# AIM2_-_FTDI_REVB.net
KiCad netlist of a schematic drawn in Altium Designer
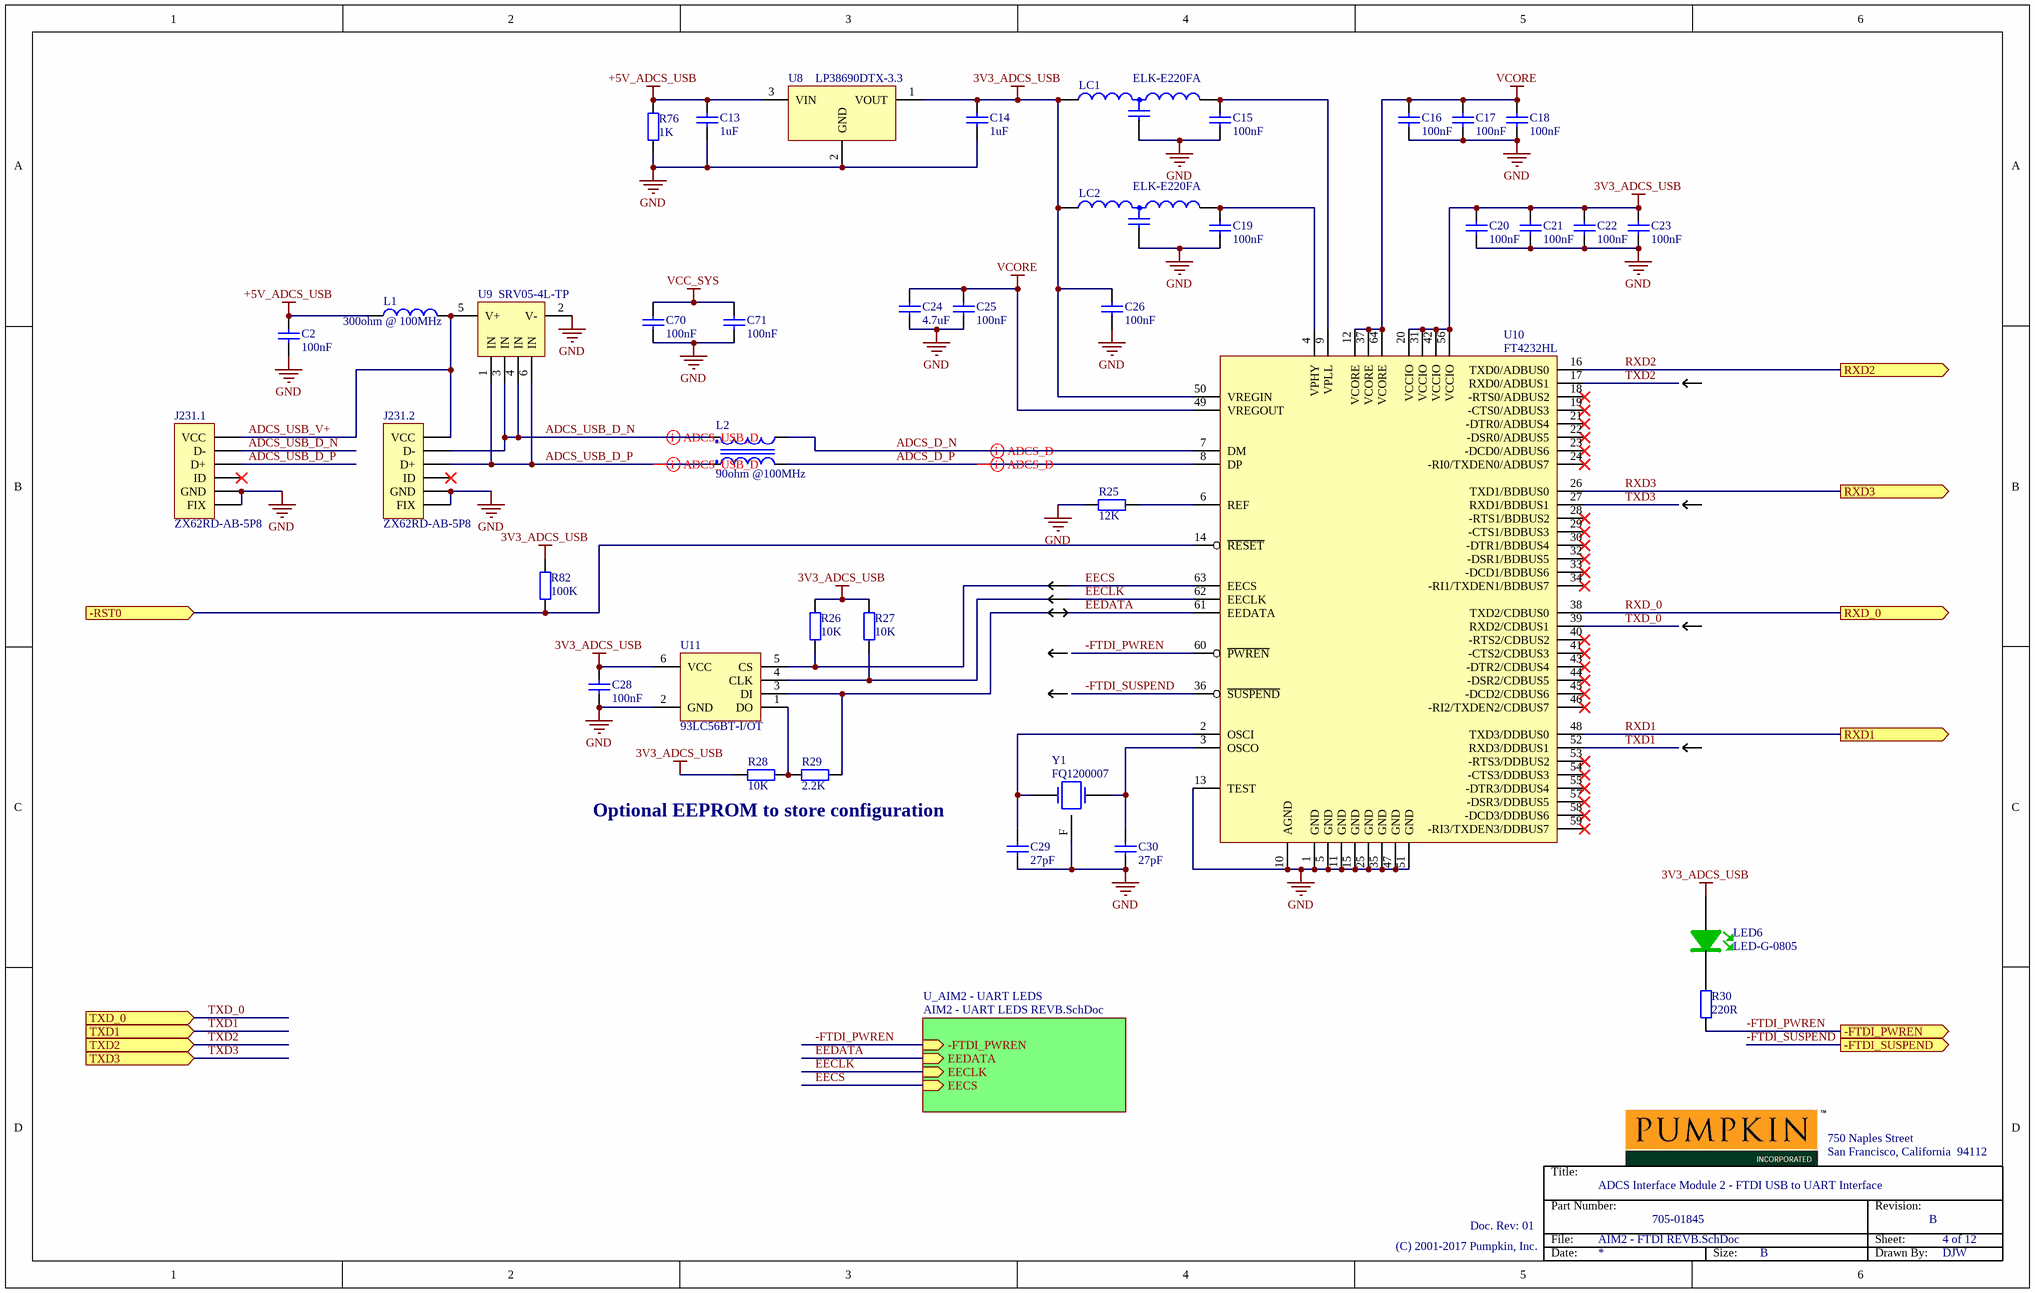
[diagram p0: AIM2 - FTDI REVB.SchDoc]

(export (version "E")
  (design (tool "Eeschema 10.0.6"))
  (components
    (comp (ref "C2")
      (value "100nF")
      (footprint "0603 CAP")
      (description "Capacitor 100nF 0603 X7R 50V 5%")
      (libsource (lib "Supernova passives") (part "Capacitor 100nF 0603"))
    )
    (comp (ref "C13")
      (value "1uF")
      (footprint "0805 CAP")
      (description "Capacitor 1uF 0805 X7R 25V 10%")
      (libsource (lib "Supernova passives") (part "Capacitor 1uF 0805"))
    )
    (comp (ref "C14")
      (value "1uF")
      (footprint "0805 CAP")
      (description "Capacitor 1uF 0805 X7R 25V 10%")
      (libsource (lib "Supernova passives") (part "Capacitor 1uF 0805"))
    )
    (comp (ref "C15")
      (value "100nF")
      (footprint "0603 CAP")
      (description "Capacitor 100nF 0603 X7R 50V 5%")
      (libsource (lib "Supernova passives") (part "Capacitor 100nF 0603"))
    )
    (comp (ref "C16")
      (value "100nF")
      (footprint "0603 CAP")
      (description "Capacitor 100nF 0603 X7R 50V 5%")
      (libsource (lib "Supernova passives") (part "Capacitor 100nF 0603"))
    )
    (comp (ref "C17")
      (value "100nF")
      (footprint "0603 CAP")
      (description "Capacitor 100nF 0603 X7R 50V 5%")
      (libsource (lib "Supernova passives") (part "Capacitor 100nF 0603"))
    )
    (comp (ref "C18")
      (value "100nF")
      (footprint "0603 CAP")
      (description "Capacitor 100nF 0603 X7R 50V 5%")
      (libsource (lib "Supernova passives") (part "Capacitor 100nF 0603"))
    )
    (comp (ref "C19")
      (value "100nF")
      (footprint "0603 CAP")
      (description "Capacitor 100nF 0603 X7R 50V 5%")
      (libsource (lib "Supernova passives") (part "Capacitor 100nF 0603"))
    )
    (comp (ref "C20")
      (value "100nF")
      (footprint "0603 CAP")
      (description "Capacitor 100nF 0603 X7R 50V 5%")
      (libsource (lib "Supernova passives") (part "Capacitor 100nF 0603"))
    )
    (comp (ref "C21")
      (value "100nF")
      (footprint "0603 CAP")
      (description "Capacitor 100nF 0603 X7R 50V 5%")
      (libsource (lib "Supernova passives") (part "Capacitor 100nF 0603"))
    )
    (comp (ref "C22")
      (value "100nF")
      (footprint "0603 CAP")
      (description "Capacitor 100nF 0603 X7R 50V 5%")
      (libsource (lib "Supernova passives") (part "Capacitor 100nF 0603"))
    )
    (comp (ref "C23")
      (value "100nF")
      (footprint "0603 CAP")
      (description "Capacitor 100nF 0603 X7R 50V 5%")
      (libsource (lib "Supernova passives") (part "Capacitor 100nF 0603"))
    )
    (comp (ref "C24")
      (value "4.7uF")
      (footprint "0805 CAP")
      (description "Capacitor 4.7uF 0805 X7R 35V 10%")
      (libsource (lib "Supernova passives") (part "Capacitor 4.7uF 0805"))
    )
    (comp (ref "C25")
      (value "100nF")
      (footprint "0603 CAP")
      (description "Capacitor 100nF 0603 X7R 50V 5%")
      (libsource (lib "Supernova passives") (part "Capacitor 100nF 0603"))
    )
    (comp (ref "C26")
      (value "100nF")
      (footprint "0603 CAP")
      (description "Capacitor 100nF 0603 X7R 50V 5%")
      (libsource (lib "Supernova passives") (part "Capacitor 100nF 0603"))
    )
    (comp (ref "C28")
      (value "100nF")
      (footprint "0603 CAP")
      (description "Capacitor 100nF 0603 X7R 50V 5%")
      (libsource (lib "Supernova passives") (part "Capacitor 100nF 0603"))
    )
    (comp (ref "C29")
      (value "27pF")
      (footprint "0402 CAP")
      (description "Capacitor 27pF 0402 NP0 50V 1%")
      (libsource (lib "Supernova passives") (part "Capacitor 27pF 0402"))
    )
    (comp (ref "C30")
      (value "27pF")
      (footprint "0402 CAP")
      (description "Capacitor 27pF 0402 NP0 50V 1%")
      (libsource (lib "Supernova passives") (part "Capacitor 27pF 0402"))
    )
    (comp (ref "C70")
      (value "100nF")
      (footprint "0603 CAP")
      (description "Capacitor 100nF 0603 X7R 50V 5%")
      (libsource (lib "Supernova passives") (part "Capacitor 100nF 0603"))
    )
    (comp (ref "C71")
      (value "100nF")
      (footprint "0603 CAP")
      (description "Capacitor 100nF 0603 X7R 50V 5%")
      (libsource (lib "Supernova passives") (part "Capacitor 100nF 0603"))
    )
    (comp (ref "J231.1")
      (value "ZX62RD-AB-5P8")
      (footprint "SM$5C$ZX62RD-AB-5P8")
      (description "Header USB Micro AB")
      (libsource (lib "Supernova") (part "ZX62RD-AB-5P8"))
    )
    (comp (ref "J231.2")
      (value "ZX62RD-AB-5P8")
      (footprint "SM$5C$ZX62RD-AB-5P8")
      (description "Header USB Micro AB")
      (libsource (lib "Supernova") (part "ZX62RD-AB-5P8"))
    )
    (comp (ref "L1")
      (value "300ohm @ 100MHz")
      (footprint "0603 IND")
      (description "Ferrite Bead 300ohm @ 100MHz")
      (libsource (lib "Supernova passives") (part "Ferrite Bead 300ohm @ 100MHz"))
    )
    (comp (ref "L2")
      (value "90ohm @100MHz")
      (footprint "DFN250P320X200-4N")
      (description "Choke Common-mode 90ohm @ 100MHz")
      (libsource (lib "Supernova passives") (part "Choke 90ohm @ 100MHz"))
    )
    (comp (ref "LC1")
      (value "ELK-E220FA")
      (footprint "ELK")
      (description "Filter LC 100MHz")
      (libsource (lib "Supernova passives") (part "LC Filter"))
    )
    (comp (ref "LC2")
      (value "ELK-E220FA")
      (footprint "ELK")
      (description "Filter LC 100MHz")
      (libsource (lib "Supernova passives") (part "LC Filter"))
    )
    (comp (ref "LED6")
      (value "LED-G-0805")
      (footprint "0805 LED-GREEN")
      (description "LED Green 0805")
      (libsource (lib "Supernova passives") (part "LED GREEN 0805"))
    )
    (comp (ref "R25")
      (value "12K")
      (footprint "0603 RES")
      (description "Resistor 12K 0603 0.1W 1%")
      (libsource (lib "Supernova passives") (part "Resistor 12K 0603"))
    )
    (comp (ref "R26")
      (value "10K")
      (footprint "0805 RES")
      (description "Resistor 10K 0805 0.125W 1%")
      (libsource (lib "Supernova passives") (part "Resistor 10K 0805"))
    )
    (comp (ref "R27")
      (value "10K")
      (footprint "0805 RES")
      (description "Resistor 10K 0805 0.125W 1%")
      (libsource (lib "Supernova passives") (part "Resistor 10K 0805"))
    )
    (comp (ref "R28")
      (value "10K")
      (footprint "0805 RES")
      (description "Resistor 10K 0805 0.125W 1%")
      (libsource (lib "") (part "Resistor 10K 0805_1"))
    )
    (comp (ref "R29")
      (value "2.2K")
      (footprint "0805 RES")
      (description "Resistor 2.2K 0805 0.125W 1%")
      (libsource (lib "Supernova passives") (part "Resistor 2K2 0805"))
    )
    (comp (ref "R30")
      (value "220R")
      (footprint "0805 RES")
      (description "Resistor 220R 0805 0.125W 1%")
      (libsource (lib "Supernova passives") (part "Resistor 220R 0805"))
    )
    (comp (ref "R76")
      (value "1K")
      (footprint "0805 RES")
      (description "Resistor 1K 0805 0.125W 1%")
      (libsource (lib "Supernova passives") (part "Resistor 1K 0805"))
    )
    (comp (ref "R82")
      (value "100K")
      (footprint "0805 RES")
      (description "Resistor 100K 0805 0.5W 1%")
      (libsource (lib "Supernova passives") (part "Resistor 100K 0805"))
    )
    (comp (ref "U8")
      (value "LP38690DTX-3.3")
      (footprint "DPAK")
      (description "Regulator 3.3V LDO")
      (libsource (lib "Supernova") (part "LP38690DTX-3.3"))
    )
    (comp (ref "U9")
      (value "SRV05-4L-TP")
      (footprint "SOT23-6")
      (description "IC ESD protection 4 input")
      (libsource (lib "Supernova") (part "SRV05-4L-TP"))
    )
    (comp (ref "U10")
      (value "FT4232HL")
      (footprint "TSQFP50P1200X1200X120_HS-65N")
      (description "IC FTDI 4 port controller")
      (libsource (lib "Supernova") (part "FT4232HL"))
    )
    (comp (ref "U11")
      (value "93LC56BT-I/OT")
      (footprint "SOT23-6")
      (description "IC Memory EEPROM 2Kbit")
      (libsource (lib "Supernova") (part "93LC56BT-I/OT"))
    )
    (comp (ref "Y1")
      (value "FQ1200007")
      (footprint "FQ Crystal")
      (description "Crystal 12MHz")
      (libsource (lib "Supernova") (part "FQ1200007"))
    )
  )
  (nets
    (net (code "1") (name "+5V_ADCS_USB") (class "Default")
      (node (ref "C13") (pin "2") (pinfunction "2_2") (pintype "passive"))
      (node (ref "C2") (pin "2") (pinfunction "2_2") (pintype "passive"))
      (node (ref "L1") (pin "1") (pinfunction "1_1") (pintype "passive"))
      (node (ref "R76") (pin "2") (pinfunction "2_2") (pintype "passive"))
      (node (ref "U8") (pin "3") (pinfunction "VIN_3") (pintype "passive"))
    )
    (net (code "2") (name "/-FTDI_PWREN") (class "Default")
      (node (ref "R30") (pin "1") (pinfunction "1_1") (pintype "passive"))
      (node (ref "U10") (pin "60") (pinfunction "~{PWREN}_60") (pintype "passive"))
    )
    (net (code "3") (name "/-FTDI_SUSPEND") (class "Default")
      (node (ref "U10") (pin "36") (pinfunction "~{SUSPEND}_36") (pintype "passive"))
    )
    (net (code "4") (name "/-RST0") (class "Default")
      (node (ref "R82") (pin "1") (pinfunction "1_1") (pintype "passive"))
      (node (ref "U10") (pin "14") (pinfunction "~{RESET}_14") (pintype "passive"))
    )
    (net (code "5") (name "/ADCS_D_N") (class "Default")
      (node (ref "L2") (pin "3") (pinfunction "3_3") (pintype "passive"))
      (node (ref "U10") (pin "7") (pinfunction "DM_7") (pintype "passive"))
    )
    (net (code "6") (name "/ADCS_D_P") (class "Default")
      (node (ref "L2") (pin "2") (pinfunction "2_2") (pintype "passive"))
      (node (ref "U10") (pin "8") (pinfunction "DP_8") (pintype "passive"))
    )
    (net (code "7") (name "/ADCS_USB_D_N") (class "Default")
      (node (ref "J231.1") (pin "2") (pinfunction "D-_2") (pintype "passive"))
      (node (ref "J231.2") (pin "2") (pinfunction "D-_2") (pintype "passive"))
      (node (ref "L2") (pin "4") (pinfunction "4_4") (pintype "passive"))
      (node (ref "U9") (pin "3") (pinfunction "IN_3") (pintype "passive"))
      (node (ref "U9") (pin "4") (pinfunction "IN_4") (pintype "passive"))
    )
    (net (code "8") (name "/ADCS_USB_D_P") (class "Default")
      (node (ref "J231.1") (pin "3") (pinfunction "D+_3") (pintype "passive"))
      (node (ref "J231.2") (pin "3") (pinfunction "D+_3") (pintype "passive"))
      (node (ref "L2") (pin "1") (pinfunction "1_1") (pintype "passive"))
      (node (ref "U9") (pin "1") (pinfunction "IN_1") (pintype "passive"))
      (node (ref "U9") (pin "6") (pinfunction "IN_6") (pintype "passive"))
    )
    (net (code "9") (name "/ADCS_USB_V+") (class "Default")
      (node (ref "J231.1") (pin "1") (pinfunction "VCC_1") (pintype "passive"))
      (node (ref "J231.2") (pin "1") (pinfunction "VCC_1") (pintype "passive"))
      (node (ref "L1") (pin "2") (pinfunction "2_2") (pintype "passive"))
      (node (ref "U9") (pin "5") (pinfunction "V+_5") (pintype "passive"))
    )
    (net (code "10") (name "/EECLK") (class "Default")
      (node (ref "R27") (pin "1") (pinfunction "1_1") (pintype "passive"))
      (node (ref "U10") (pin "62") (pinfunction "EECLK_62") (pintype "passive"))
      (node (ref "U11") (pin "4") (pinfunction "CLK_4") (pintype "passive"))
    )
    (net (code "11") (name "/EECS") (class "Default")
      (node (ref "R26") (pin "1") (pinfunction "1_1") (pintype "passive"))
      (node (ref "U10") (pin "63") (pinfunction "EECS_63") (pintype "passive"))
      (node (ref "U11") (pin "5") (pinfunction "CS_5") (pintype "passive"))
    )
    (net (code "12") (name "/EEDATA") (class "Default")
      (node (ref "R29") (pin "2") (pinfunction "2_2") (pintype "passive"))
      (node (ref "U10") (pin "61") (pinfunction "EEDATA_61") (pintype "passive"))
      (node (ref "U11") (pin "3") (pinfunction "DI_3") (pintype "passive"))
    )
    (net (code "13") (name "/RXD1") (class "Default")
      (node (ref "U10") (pin "48") (pinfunction "TXD3/DDBUS0_48") (pintype "passive"))
    )
    (net (code "14") (name "/RXD2") (class "Default")
      (node (ref "U10") (pin "16") (pinfunction "TXD0/ADBUS0_16") (pintype "passive"))
    )
    (net (code "15") (name "/RXD3") (class "Default")
      (node (ref "U10") (pin "26") (pinfunction "TXD1/BDBUS0_26") (pintype "passive"))
    )
    (net (code "16") (name "/RXD_0") (class "Default")
      (node (ref "U10") (pin "38") (pinfunction "TXD2/CDBUS0_38") (pintype "passive"))
    )
    (net (code "17") (name "/TXD1") (class "Default")
      (node (ref "U10") (pin "52") (pinfunction "RXD3/DDBUS1_52") (pintype "passive"))
    )
    (net (code "18") (name "/TXD2") (class "Default")
      (node (ref "U10") (pin "17") (pinfunction "RXD0/ADBUS1_17") (pintype "passive"))
    )
    (net (code "19") (name "/TXD3") (class "Default")
      (node (ref "U10") (pin "27") (pinfunction "RXD1/BDBUS1_27") (pintype "passive"))
    )
    (net (code "20") (name "/TXD_0") (class "Default")
      (node (ref "U10") (pin "39") (pinfunction "RXD2/CDBUS1_39") (pintype "passive"))
    )
    (net (code "21") (name "3V3_ADCS_USB") (class "Default")
      (node (ref "C14") (pin "2") (pinfunction "2_2") (pintype "passive"))
      (node (ref "C20") (pin "2") (pinfunction "2_2") (pintype "passive"))
      (node (ref "C21") (pin "2") (pinfunction "2_2") (pintype "passive"))
      (node (ref "C22") (pin "2") (pinfunction "2_2") (pintype "passive"))
      (node (ref "C23") (pin "2") (pinfunction "2_2") (pintype "passive"))
      (node (ref "C26") (pin "2") (pinfunction "2_2") (pintype "passive"))
      (node (ref "C28") (pin "2") (pinfunction "2_2") (pintype "passive"))
      (node (ref "LC1") (pin "1") (pinfunction "1_1") (pintype "passive"))
      (node (ref "LC2") (pin "1") (pinfunction "1_1") (pintype "passive"))
      (node (ref "LED6") (pin "2") (pinfunction "2_2") (pintype "passive"))
      (node (ref "R26") (pin "2") (pinfunction "2_2") (pintype "passive"))
      (node (ref "R27") (pin "2") (pinfunction "2_2") (pintype "passive"))
      (node (ref "R28") (pin "1") (pinfunction "1_1") (pintype "passive"))
      (node (ref "R82") (pin "2") (pinfunction "2_2") (pintype "passive"))
      (node (ref "U10") (pin "20") (pinfunction "VCCIO_20") (pintype "passive"))
      (node (ref "U10") (pin "31") (pinfunction "VCCIO_31") (pintype "passive"))
      (node (ref "U10") (pin "42") (pinfunction "VCCIO_42") (pintype "passive"))
      (node (ref "U10") (pin "50") (pinfunction "VREGIN_50") (pintype "passive"))
      (node (ref "U10") (pin "56") (pinfunction "VCCIO_56") (pintype "passive"))
      (node (ref "U11") (pin "6") (pinfunction "VCC_6") (pintype "passive"))
      (node (ref "U8") (pin "1") (pinfunction "VOUT_1") (pintype "passive"))
    )
    (net (code "22") (name "GND") (class "Default")
      (node (ref "C13") (pin "1") (pinfunction "1_1") (pintype "passive"))
      (node (ref "C14") (pin "1") (pinfunction "1_1") (pintype "passive"))
      (node (ref "C15") (pin "1") (pinfunction "1_1") (pintype "passive"))
      (node (ref "C16") (pin "1") (pinfunction "1_1") (pintype "passive"))
      (node (ref "C17") (pin "1") (pinfunction "1_1") (pintype "passive"))
      (node (ref "C18") (pin "1") (pinfunction "1_1") (pintype "passive"))
      (node (ref "C19") (pin "1") (pinfunction "1_1") (pintype "passive"))
      (node (ref "C2") (pin "1") (pinfunction "1_1") (pintype "passive"))
      (node (ref "C20") (pin "1") (pinfunction "1_1") (pintype "passive"))
      (node (ref "C21") (pin "1") (pinfunction "1_1") (pintype "passive"))
      (node (ref "C22") (pin "1") (pinfunction "1_1") (pintype "passive"))
      (node (ref "C23") (pin "1") (pinfunction "1_1") (pintype "passive"))
      (node (ref "C24") (pin "1") (pinfunction "1_1") (pintype "passive"))
      (node (ref "C25") (pin "1") (pinfunction "1_1") (pintype "passive"))
      (node (ref "C26") (pin "1") (pinfunction "1_1") (pintype "passive"))
      (node (ref "C28") (pin "1") (pinfunction "1_1") (pintype "passive"))
      (node (ref "C29") (pin "1") (pinfunction "1_1") (pintype "passive"))
      (node (ref "C30") (pin "1") (pinfunction "1_1") (pintype "passive"))
      (node (ref "C70") (pin "1") (pinfunction "1_1") (pintype "passive"))
      (node (ref "C71") (pin "1") (pinfunction "1_1") (pintype "passive"))
      (node (ref "J231.1") (pin "5") (pinfunction "GND_5") (pintype "passive"))
      (node (ref "J231.1") (pin "F") (pinfunction "FIX_F") (pintype "passive"))
      (node (ref "J231.2") (pin "5") (pinfunction "GND_5") (pintype "passive"))
      (node (ref "J231.2") (pin "F") (pinfunction "FIX_F") (pintype "passive"))
      (node (ref "LC1") (pin "2") (pinfunction "2_2") (pintype "passive"))
      (node (ref "LC2") (pin "2") (pinfunction "2_2") (pintype "passive"))
      (node (ref "R25") (pin "1") (pinfunction "1_1") (pintype "passive"))
      (node (ref "R76") (pin "1") (pinfunction "1_1") (pintype "passive"))
      (node (ref "U10") (pin "1") (pinfunction "GND_1") (pintype "passive"))
      (node (ref "U10") (pin "10") (pinfunction "AGND_10") (pintype "passive"))
      (node (ref "U10") (pin "11") (pinfunction "GND_11") (pintype "passive"))
      (node (ref "U10") (pin "13") (pinfunction "TEST_13") (pintype "passive"))
      (node (ref "U10") (pin "15") (pinfunction "GND_15") (pintype "passive"))
      (node (ref "U10") (pin "25") (pinfunction "GND_25") (pintype "passive"))
      (node (ref "U10") (pin "35") (pinfunction "GND_35") (pintype "passive"))
      (node (ref "U10") (pin "47") (pinfunction "GND_47") (pintype "passive"))
      (node (ref "U10") (pin "5") (pinfunction "GND_5") (pintype "passive"))
      (node (ref "U10") (pin "51") (pinfunction "GND_51") (pintype "passive"))
      (node (ref "U11") (pin "2") (pinfunction "GND_2") (pintype "passive"))
      (node (ref "U8") (pin "2") (pinfunction "GND_2") (pintype "passive"))
      (node (ref "U9") (pin "2") (pinfunction "V-_2") (pintype "passive"))
      (node (ref "Y1") (pin "F") (pinfunction "1_F") (pintype "passive"))
    )
    (net (code "23") (name "Net-(LED6-Pad1)") (class "Default")
      (node (ref "LED6") (pin "1") (pinfunction "1_1") (pintype "passive"))
      (node (ref "R30") (pin "2") (pinfunction "2_2") (pintype "passive"))
    )
    (net (code "24") (name "Net-(U10-OSCI)") (class "Default")
      (node (ref "C29") (pin "2") (pinfunction "2_2") (pintype "passive"))
      (node (ref "U10") (pin "2") (pinfunction "OSCI_2") (pintype "passive"))
      (node (ref "Y1") (pin "1") (pinfunction "1_1") (pintype "passive"))
    )
    (net (code "25") (name "Net-(U10-OSCO)") (class "Default")
      (node (ref "C30") (pin "2") (pinfunction "2_2") (pintype "passive"))
      (node (ref "U10") (pin "3") (pinfunction "OSCO_3") (pintype "passive"))
      (node (ref "Y1") (pin "3") (pinfunction "1_3") (pintype "passive"))
    )
    (net (code "26") (name "Net-(U10-REF)") (class "Default")
      (node (ref "R25") (pin "2") (pinfunction "2_2") (pintype "passive"))
      (node (ref "U10") (pin "6") (pinfunction "REF_6") (pintype "passive"))
    )
    (net (code "27") (name "Net-(U10-VPHY)") (class "Default")
      (node (ref "C19") (pin "2") (pinfunction "2_2") (pintype "passive"))
      (node (ref "LC2") (pin "3") (pinfunction "3_3") (pintype "passive"))
      (node (ref "U10") (pin "4") (pinfunction "VPHY_4") (pintype "passive"))
    )
    (net (code "28") (name "Net-(U10-VPLL)") (class "Default")
      (node (ref "C15") (pin "2") (pinfunction "2_2") (pintype "passive"))
      (node (ref "LC1") (pin "3") (pinfunction "3_3") (pintype "passive"))
      (node (ref "U10") (pin "9") (pinfunction "VPLL_9") (pintype "passive"))
    )
    (net (code "29") (name "Net-(U11-DO)") (class "Default")
      (node (ref "R28") (pin "2") (pinfunction "2_2") (pintype "passive"))
      (node (ref "R29") (pin "1") (pinfunction "1_1") (pintype "passive"))
      (node (ref "U11") (pin "1") (pinfunction "DO_1") (pintype "passive"))
    )
    (net (code "30") (name "VCC_SYS") (class "Default")
      (node (ref "C70") (pin "2") (pinfunction "2_2") (pintype "passive"))
      (node (ref "C71") (pin "2") (pinfunction "2_2") (pintype "passive"))
    )
    (net (code "31") (name "VCORE") (class "Default")
      (node (ref "C16") (pin "2") (pinfunction "2_2") (pintype "passive"))
      (node (ref "C17") (pin "2") (pinfunction "2_2") (pintype "passive"))
      (node (ref "C18") (pin "2") (pinfunction "2_2") (pintype "passive"))
      (node (ref "C24") (pin "2") (pinfunction "2_2") (pintype "passive"))
      (node (ref "C25") (pin "2") (pinfunction "2_2") (pintype "passive"))
      (node (ref "U10") (pin "12") (pinfunction "VCORE_12") (pintype "passive"))
      (node (ref "U10") (pin "37") (pinfunction "VCORE_37") (pintype "passive"))
      (node (ref "U10") (pin "49") (pinfunction "VREGOUT_49") (pintype "passive"))
      (node (ref "U10") (pin "64") (pinfunction "VCORE_64") (pintype "passive"))
    )
    (net (code "32") (name "unconnected-(J231.1-ID-Pad4)") (class "Default")
      (node (ref "J231.1") (pin "4") (pinfunction "ID_4") (pintype "passive+no_connect"))
    )
    (net (code "33") (name "unconnected-(J231.2-ID-Pad4)") (class "Default")
      (node (ref "J231.2") (pin "4") (pinfunction "ID_4") (pintype "passive+no_connect"))
    )
    (net (code "34") (name "unconnected-(U10--CTS0{slash}ADBUS3-Pad19)") (class "Default")
      (node (ref "U10") (pin "19") (pinfunction "-CTS0/ADBUS3_19") (pintype "passive+no_connect"))
    )
    (net (code "35") (name "unconnected-(U10--CTS1{slash}BDBUS3-Pad29)") (class "Default")
      (node (ref "U10") (pin "29") (pinfunction "-CTS1/BDBUS3_29") (pintype "passive+no_connect"))
    )
    (net (code "36") (name "unconnected-(U10--CTS2{slash}CDBUS3-Pad41)") (class "Default")
      (node (ref "U10") (pin "41") (pinfunction "-CTS2/CDBUS3_41") (pintype "passive+no_connect"))
    )
    (net (code "37") (name "unconnected-(U10--CTS3{slash}DDBUS3-Pad54)") (class "Default")
      (node (ref "U10") (pin "54") (pinfunction "-CTS3/DDBUS3_54") (pintype "passive+no_connect"))
    )
    (net (code "38") (name "unconnected-(U10--DCD0{slash}ADBUS6-Pad23)") (class "Default")
      (node (ref "U10") (pin "23") (pinfunction "-DCD0/ADBUS6_23") (pintype "passive+no_connect"))
    )
    (net (code "39") (name "unconnected-(U10--DCD1{slash}BDBUS6-Pad33)") (class "Default")
      (node (ref "U10") (pin "33") (pinfunction "-DCD1/BDBUS6_33") (pintype "passive+no_connect"))
    )
    (net (code "40") (name "unconnected-(U10--DCD2{slash}CDBUS6-Pad45)") (class "Default")
      (node (ref "U10") (pin "45") (pinfunction "-DCD2/CDBUS6_45") (pintype "passive+no_connect"))
    )
    (net (code "41") (name "unconnected-(U10--DCD3{slash}DDBUS6-Pad58)") (class "Default")
      (node (ref "U10") (pin "58") (pinfunction "-DCD3/DDBUS6_58") (pintype "passive+no_connect"))
    )
    (net (code "42") (name "unconnected-(U10--DSR0{slash}ADBUS5-Pad22)") (class "Default")
      (node (ref "U10") (pin "22") (pinfunction "-DSR0/ADBUS5_22") (pintype "passive+no_connect"))
    )
    (net (code "43") (name "unconnected-(U10--DSR1{slash}BDBUS5-Pad32)") (class "Default")
      (node (ref "U10") (pin "32") (pinfunction "-DSR1/BDBUS5_32") (pintype "passive+no_connect"))
    )
    (net (code "44") (name "unconnected-(U10--DSR2{slash}CDBUS5-Pad44)") (class "Default")
      (node (ref "U10") (pin "44") (pinfunction "-DSR2/CDBUS5_44") (pintype "passive+no_connect"))
    )
    (net (code "45") (name "unconnected-(U10--DSR3{slash}DDBUS5-Pad57)") (class "Default")
      (node (ref "U10") (pin "57") (pinfunction "-DSR3/DDBUS5_57") (pintype "passive+no_connect"))
    )
    (net (code "46") (name "unconnected-(U10--DTR0{slash}ADBUS4-Pad21)") (class "Default")
      (node (ref "U10") (pin "21") (pinfunction "-DTR0/ADBUS4_21") (pintype "passive+no_connect"))
    )
    (net (code "47") (name "unconnected-(U10--DTR1{slash}BDBUS4-Pad30)") (class "Default")
      (node (ref "U10") (pin "30") (pinfunction "-DTR1/BDBUS4_30") (pintype "passive+no_connect"))
    )
    (net (code "48") (name "unconnected-(U10--DTR2{slash}CDBUS4-Pad43)") (class "Default")
      (node (ref "U10") (pin "43") (pinfunction "-DTR2/CDBUS4_43") (pintype "passive+no_connect"))
    )
    (net (code "49") (name "unconnected-(U10--DTR3{slash}DDBUS4-Pad55)") (class "Default")
      (node (ref "U10") (pin "55") (pinfunction "-DTR3/DDBUS4_55") (pintype "passive+no_connect"))
    )
    (net (code "50") (name "unconnected-(U10--RI0{slash}TXDEN0{slash}ADBUS7-Pad24)") (class "Default")
      (node (ref "U10") (pin "24") (pinfunction "-RI0/TXDEN0/ADBUS7_24") (pintype "passive+no_connect"))
    )
    (net (code "51") (name "unconnected-(U10--RI1{slash}TXDEN1{slash}BDBUS7-Pad34)") (class "Default")
      (node (ref "U10") (pin "34") (pinfunction "-RI1/TXDEN1/BDBUS7_34") (pintype "passive+no_connect"))
    )
    (net (code "52") (name "unconnected-(U10--RI2{slash}TXDEN2{slash}CDBUS7-Pad46)") (class "Default")
      (node (ref "U10") (pin "46") (pinfunction "-RI2/TXDEN2/CDBUS7_46") (pintype "passive+no_connect"))
    )
    (net (code "53") (name "unconnected-(U10--RI3{slash}TXDEN3{slash}DDBUS7-Pad59)") (class "Default")
      (node (ref "U10") (pin "59") (pinfunction "-RI3/TXDEN3/DDBUS7_59") (pintype "passive+no_connect"))
    )
    (net (code "54") (name "unconnected-(U10--RTS0{slash}ADBUS2-Pad18)") (class "Default")
      (node (ref "U10") (pin "18") (pinfunction "-RTS0/ADBUS2_18") (pintype "passive+no_connect"))
    )
    (net (code "55") (name "unconnected-(U10--RTS1{slash}BDBUS2-Pad28)") (class "Default")
      (node (ref "U10") (pin "28") (pinfunction "-RTS1/BDBUS2_28") (pintype "passive+no_connect"))
    )
    (net (code "56") (name "unconnected-(U10--RTS2{slash}CDBUS2-Pad40)") (class "Default")
      (node (ref "U10") (pin "40") (pinfunction "-RTS2/CDBUS2_40") (pintype "passive+no_connect"))
    )
    (net (code "57") (name "unconnected-(U10--RTS3{slash}DDBUS2-Pad53)") (class "Default")
      (node (ref "U10") (pin "53") (pinfunction "-RTS3/DDBUS2_53") (pintype "passive+no_connect"))
    )
  )
)
